# USB_C_Filter.net
KiCad netlist of a schematic drawn in Altium Designer
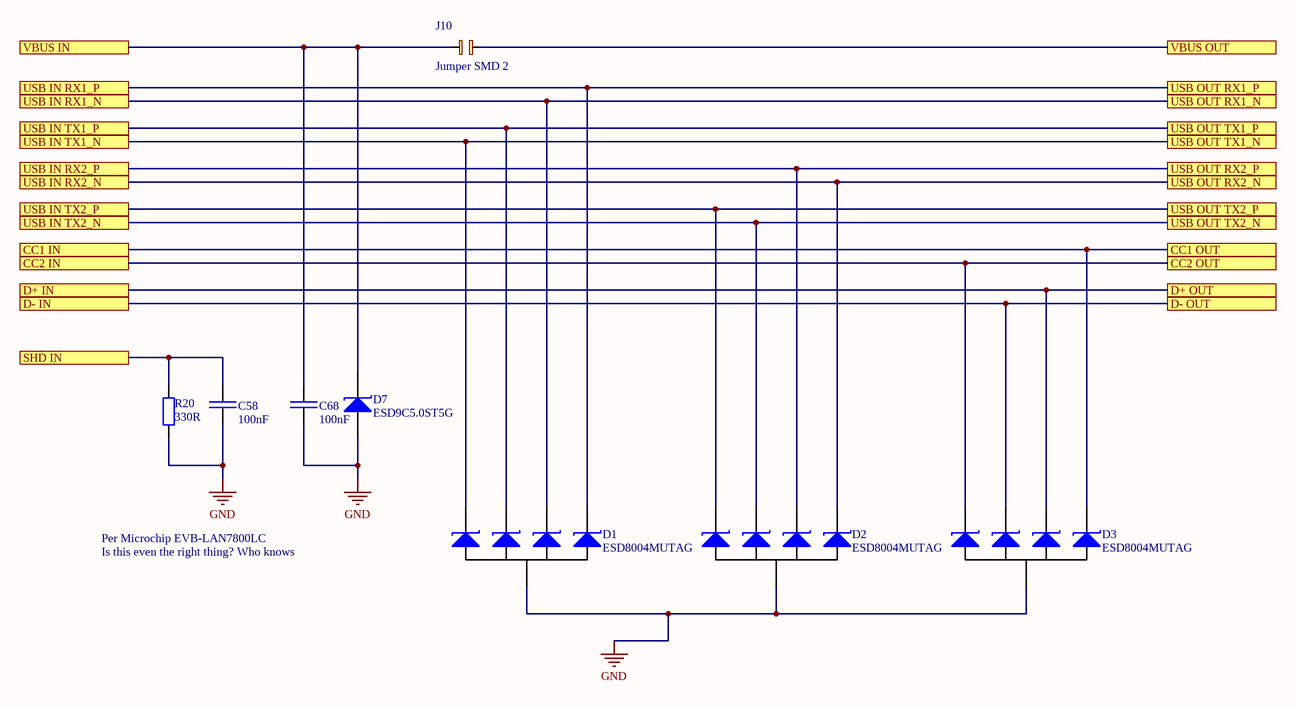
[diagram p0: USB C Filter.SchDoc]

(export (version "E")
  (design (tool "Eeschema 10.0.6"))
  (components
    (comp (ref "C58")
      (value "100nF")
      (footprint "CAP_SM0603_YAGEOCC2_N")
      (description "CAP 100nF SM0603 X7R 50V YAGEO CC2")
      (fields
        (field (name "MANUFACTURER") "Yageo")
        (field (name "MANUFACTURER PART NUMBER") "CC0603KRX7R9BB104")
      )
      (libsource (lib "Yageo") (part "CC0603KRX7R9BB104"))
    )
    (comp (ref "C68")
      (value "100nF")
      (footprint "CAP_SM0603_YAGEOCC2_N")
      (description "CAP 100nF SM0603 X7R 50V YAGEO CC2")
      (fields
        (field (name "MANUFACTURER") "Yageo")
        (field (name "MANUFACTURER PART NUMBER") "CC0603KRX7R9BB104")
      )
      (libsource (lib "Yageo") (part "CC0603KRX7R9BB104"))
    )
    (comp (ref "D1")
      (value "ESD8004MUTAG")
      (footprint "ESD8004MUTAG")
      (description "TVS DIODE 3.3VWM 8VC 10UDFN")
      (libsource (lib "KBuchka-IntLib") (part "ESD8004MUTAG"))
    )
    (comp (ref "D2")
      (value "ESD8004MUTAG")
      (footprint "ESD8004MUTAG")
      (description "TVS DIODE 3.3VWM 8VC 10UDFN")
      (libsource (lib "KBuchka-IntLib") (part "ESD8004MUTAG"))
    )
    (comp (ref "D3")
      (value "ESD8004MUTAG")
      (footprint "ESD8004MUTAG")
      (description "TVS DIODE 3.3VWM 8VC 10UDFN")
      (libsource (lib "KBuchka-IntLib") (part "ESD8004MUTAG"))
    )
    (comp (ref "D7")
      (value "ESD9C5.0ST5G")
      (footprint "SODFL100X40-2N - ESD9C5.0ST5G")
      (description "TVS DIODE 5VWM SOD923")
      (libsource (lib "KBuchka-IntLib") (part "ESD9C5.0ST5G"))
    )
    (comp (ref "J10")
      (value "Jumper SMD 2")
      (footprint "Jumper SMD 2")
      (libsource (lib "KBuchka-IntLib") (part "Jumper SMD 2"))
    )
    (comp (ref "R20")
      (value "330R")
      (footprint "RES_SM0603_YAGEORC_N")
      (description "RES 330R SM0603 YAGEO RC_L")
      (fields
        (field (name "MANUFACTURER") "Yageo")
        (field (name "MANUFACTURER PART NUMBER") "RC0603FR-07330RL")
      )
      (libsource (lib "Yageo") (part "RC0603FR-07330RL"))
    )
  )
  (nets
    (net (code "1") (name "/CC1 IN") (class "Default")
      (node (ref "D3") (pin "5") (pinfunction "K_5") (pintype "passive"))
    )
    (net (code "2") (name "/CC2 IN") (class "Default")
      (node (ref "D3") (pin "1") (pinfunction "K_1") (pintype "passive"))
    )
    (net (code "3") (name "/D+ IN") (class "Default")
      (node (ref "D3") (pin "4") (pinfunction "K_4") (pintype "passive"))
    )
    (net (code "4") (name "/D- IN") (class "Default")
      (node (ref "D3") (pin "2") (pinfunction "K_2") (pintype "passive"))
    )
    (net (code "5") (name "/SHD IN") (class "Default")
      (node (ref "C58") (pin "1") (pintype "passive"))
      (node (ref "R20") (pin "2") (pintype "passive"))
    )
    (net (code "6") (name "/USB IN RX1_N") (class "Default")
      (node (ref "D1") (pin "4") (pinfunction "K_4") (pintype "passive"))
    )
    (net (code "7") (name "/USB IN RX1_P") (class "Default")
      (node (ref "D1") (pin "5") (pinfunction "K_5") (pintype "passive"))
    )
    (net (code "8") (name "/USB IN RX2_N") (class "Default")
      (node (ref "D2") (pin "5") (pinfunction "K_5") (pintype "passive"))
    )
    (net (code "9") (name "/USB IN RX2_P") (class "Default")
      (node (ref "D2") (pin "4") (pinfunction "K_4") (pintype "passive"))
    )
    (net (code "10") (name "/USB IN TX1_N") (class "Default")
      (node (ref "D1") (pin "1") (pinfunction "K_1") (pintype "passive"))
    )
    (net (code "11") (name "/USB IN TX1_P") (class "Default")
      (node (ref "D1") (pin "2") (pinfunction "K_2") (pintype "passive"))
    )
    (net (code "12") (name "/USB IN TX2_N") (class "Default")
      (node (ref "D2") (pin "2") (pinfunction "K_2") (pintype "passive"))
    )
    (net (code "13") (name "/USB IN TX2_P") (class "Default")
      (node (ref "D2") (pin "1") (pinfunction "K_1") (pintype "passive"))
    )
    (net (code "14") (name "/VBUS IN") (class "Default")
      (node (ref "C68") (pin "1") (pintype "passive"))
      (node (ref "D7") (pin "1") (pinfunction "K_1") (pintype "passive"))
      (node (ref "J10") (pin "2") (pinfunction "2_2") (pintype "passive"))
    )
    (net (code "15") (name "/VBUS OUT") (class "Default")
      (node (ref "J10") (pin "1") (pinfunction "1_1") (pintype "passive"))
    )
    (net (code "16") (name "GND") (class "Default")
      (node (ref "C58") (pin "2") (pintype "passive"))
      (node (ref "C68") (pin "2") (pintype "passive"))
      (node (ref "D1") (pin "GND") (pinfunction "A_GND") (pintype "passive"))
      (node (ref "D2") (pin "GND") (pinfunction "A_GND") (pintype "passive"))
      (node (ref "D3") (pin "GND") (pinfunction "A_GND") (pintype "passive"))
      (node (ref "D7") (pin "2") (pinfunction "2_2") (pintype "passive"))
      (node (ref "R20") (pin "1") (pintype "passive"))
    )
  )
)
